# i2c_rom.net
KiCad netlist of a schematic drawn in EAGLE
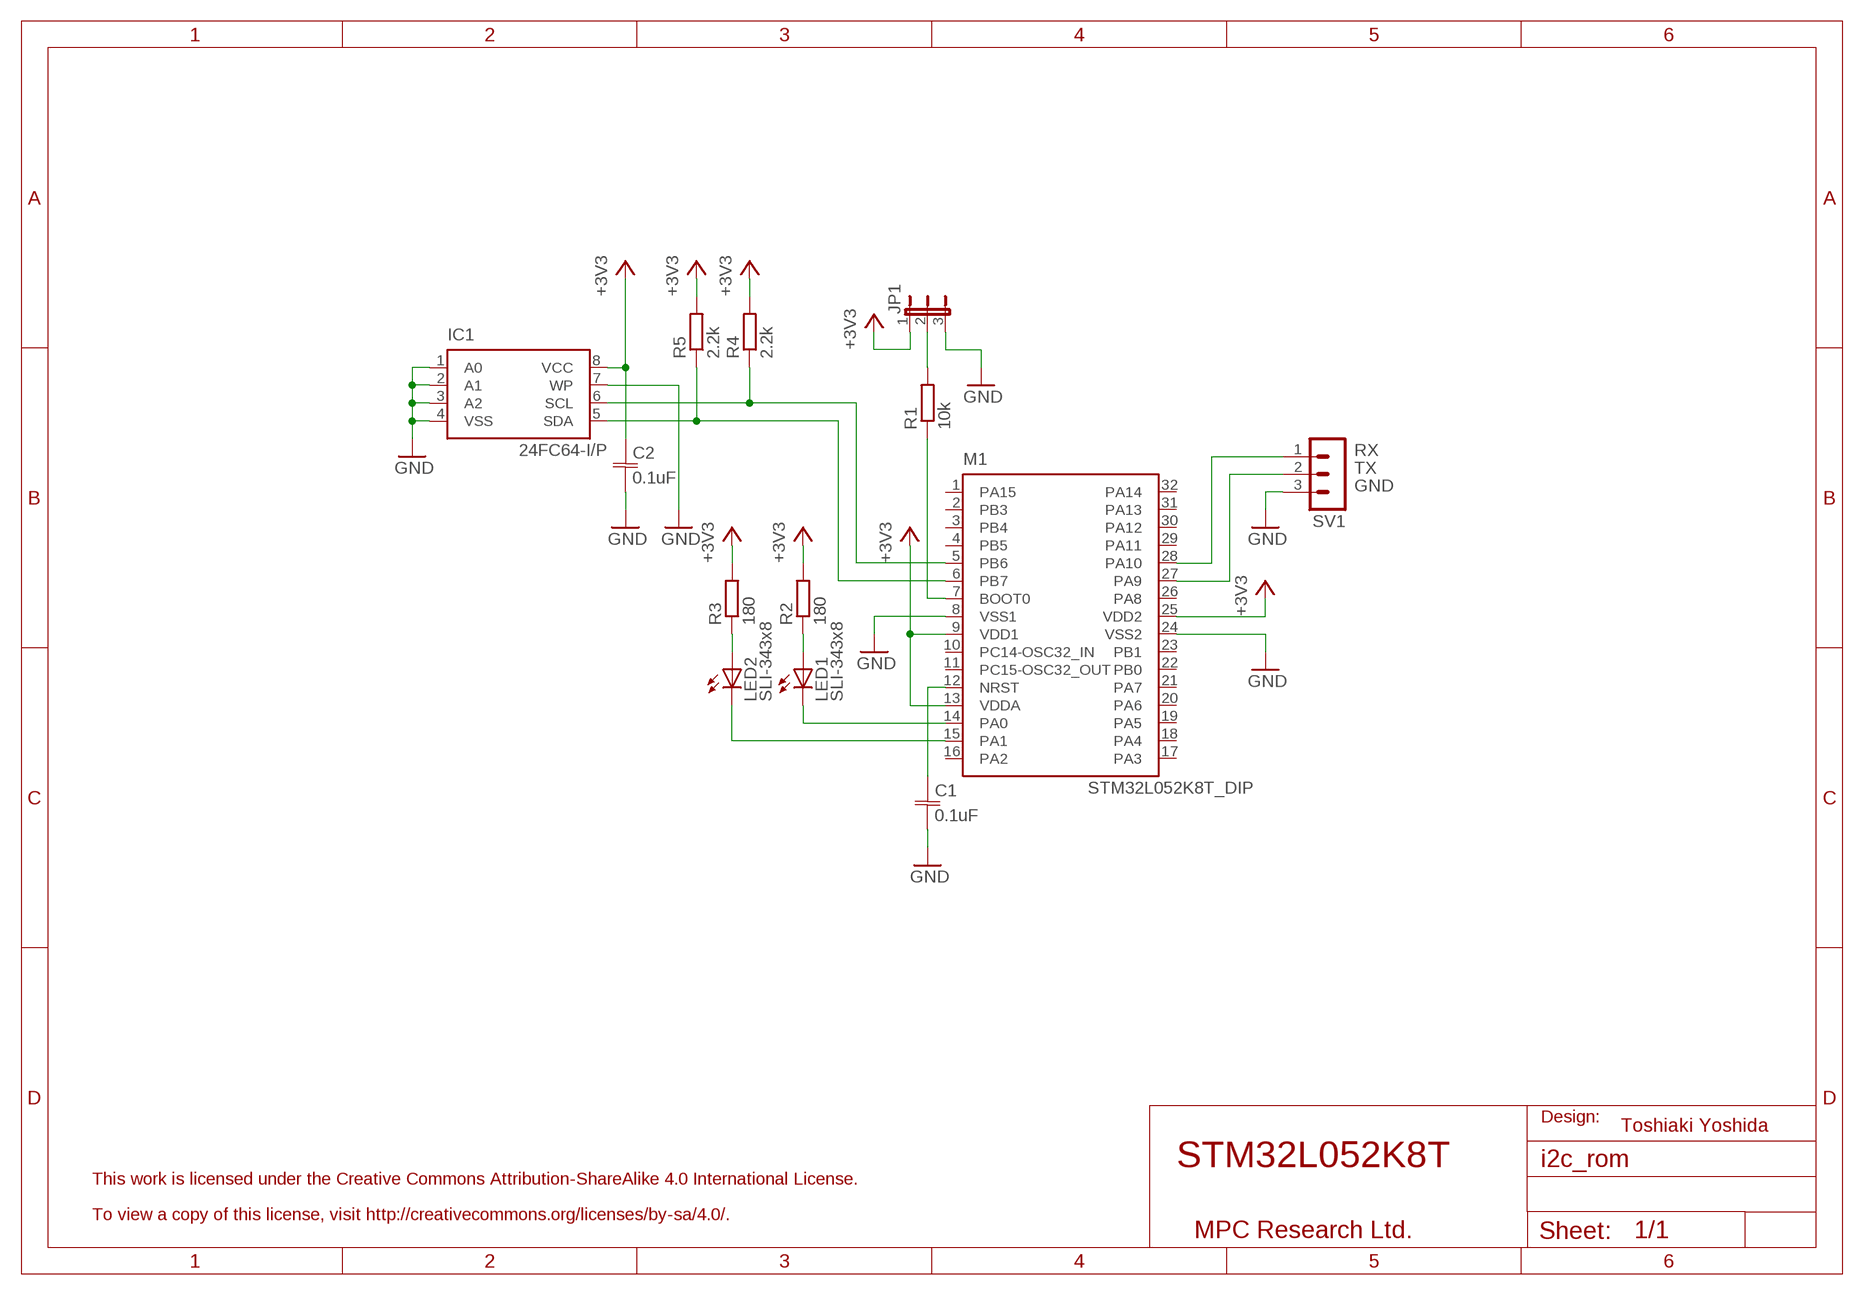
[diagram p0: schematic, sheet 1]

(export (version "E")
  (design (tool "Eeschema 10.0.6"))
  (components
    (comp (ref "C1")
      (value "0.1uF")
      (footprint "eagle-import:C050-024X044")
      (libsource (lib "eagle-import") (part "C-JIS050-024X044"))
    )
    (comp (ref "C2")
      (value "0.1uF")
      (footprint "eagle-import:C050-024X044")
      (libsource (lib "eagle-import") (part "C-JIS050-024X044"))
    )
    (comp (ref "IC1")
      (value "24FC64-I/P")
      (footprint "eagle-import:DIL8")
      (libsource (lib "eagle-import") (part "24/PFC64-I"))
    )
    (comp (ref "JP1")
      (value "JP2E")
      (footprint "eagle-import:JP2")
      (libsource (lib "eagle-import") (part "JP2E"))
    )
    (comp (ref "LED1")
      (value "SLI-343x8")
      (footprint "eagle-import:LED3MM")
      (libsource (lib "eagle-import") (part "LED3MM"))
    )
    (comp (ref "LED2")
      (value "SLI-343x8")
      (footprint "eagle-import:LED3MM")
      (libsource (lib "eagle-import") (part "LED3MM"))
    )
    (comp (ref "M1")
      (value "STM32L052K8T_DIP")
      (footprint "eagle-import:DIP32")
      (libsource (lib "eagle-import") (part "STM32L052K8T_DIP"))
    )
    (comp (ref "R1")
      (value "10k")
      (footprint "eagle-import:0207_2V")
      (libsource (lib "eagle-import") (part "R-EU_0207/2V"))
    )
    (comp (ref "R2")
      (value "180")
      (footprint "eagle-import:0207_2V")
      (libsource (lib "eagle-import") (part "R-EU_0207/2V"))
    )
    (comp (ref "R3")
      (value "180")
      (footprint "eagle-import:0207_2V")
      (libsource (lib "eagle-import") (part "R-EU_0207/2V"))
    )
    (comp (ref "R4")
      (value "2.2k")
      (footprint "eagle-import:0207_2V")
      (libsource (lib "eagle-import") (part "R-EU_0207/2V"))
    )
    (comp (ref "R5")
      (value "2.2k")
      (footprint "eagle-import:0207_2V")
      (libsource (lib "eagle-import") (part "R-EU_0207/2V"))
    )
    (comp (ref "SV1")
      (value "MA03-1")
      (footprint "eagle-import:MA03-1")
      (libsource (lib "eagle-import") (part "MA03-1"))
    )
  )
  (nets
    (net (code "1") (name "+3V3") (class "Default")
      (node (ref "C2") (pin "1") (pinfunction "1_1") (pintype "passive"))
      (node (ref "IC1") (pin "8") (pinfunction "VCC_8") (pintype "power_in"))
      (node (ref "JP1") (pin "1") (pinfunction "1_1") (pintype "passive"))
      (node (ref "M1") (pin "13") (pinfunction "VDDA_13") (pintype "power_in"))
      (node (ref "M1") (pin "25") (pinfunction "VDD2_25") (pintype "bidirectional"))
      (node (ref "M1") (pin "9") (pinfunction "VDD1_9") (pintype "power_in"))
      (node (ref "R2") (pin "2") (pinfunction "2_2") (pintype "passive"))
      (node (ref "R3") (pin "2") (pinfunction "2_2") (pintype "passive"))
      (node (ref "R4") (pin "2") (pinfunction "2_2") (pintype "passive"))
      (node (ref "R5") (pin "2") (pinfunction "2_2") (pintype "passive"))
    )
    (net (code "2") (name "GND") (class "Default")
      (node (ref "C1") (pin "2") (pinfunction "2_2") (pintype "passive"))
      (node (ref "C2") (pin "2") (pinfunction "2_2") (pintype "passive"))
      (node (ref "IC1") (pin "1") (pinfunction "A0_1") (pintype "input"))
      (node (ref "IC1") (pin "2") (pinfunction "A1_2") (pintype "input"))
      (node (ref "IC1") (pin "3") (pinfunction "A2_3") (pintype "input"))
      (node (ref "IC1") (pin "4") (pinfunction "VSS_4") (pintype "power_in"))
      (node (ref "IC1") (pin "7") (pinfunction "WP_7") (pintype "input"))
      (node (ref "JP1") (pin "3") (pinfunction "3_3") (pintype "passive"))
      (node (ref "M1") (pin "24") (pinfunction "VSS2_24") (pintype "power_in"))
      (node (ref "M1") (pin "8") (pinfunction "VSS1_8") (pintype "power_in"))
      (node (ref "SV1") (pin "3") (pinfunction "3_3") (pintype "passive"))
    )
    (net (code "3") (name "Net-(IC1-SCL)") (class "Default")
      (node (ref "IC1") (pin "6") (pinfunction "SCL_6") (pintype "input"))
      (node (ref "M1") (pin "5") (pinfunction "PB6_5") (pintype "bidirectional"))
      (node (ref "R4") (pin "1") (pinfunction "1_1") (pintype "passive"))
    )
    (net (code "4") (name "Net-(IC1-SDA)") (class "Default")
      (node (ref "IC1") (pin "5") (pinfunction "SDA_5") (pintype "open_collector"))
      (node (ref "M1") (pin "6") (pinfunction "PB7_6") (pintype "bidirectional"))
      (node (ref "R5") (pin "1") (pinfunction "1_1") (pintype "passive"))
    )
    (net (code "5") (name "Net-(JP1-Pad2)") (class "Default")
      (node (ref "JP1") (pin "2") (pinfunction "2_2") (pintype "passive"))
      (node (ref "R1") (pin "2") (pinfunction "2_2") (pintype "passive"))
    )
    (net (code "6") (name "Net-(LED1-C)") (class "Default")
      (node (ref "LED1") (pin "K") (pinfunction "C_K") (pintype "passive"))
      (node (ref "M1") (pin "14") (pinfunction "PA0_14") (pintype "bidirectional"))
    )
    (net (code "7") (name "Net-(LED1-PadA)") (class "Default")
      (node (ref "LED1") (pin "A") (pinfunction "A_A") (pintype "passive"))
      (node (ref "R2") (pin "1") (pinfunction "1_1") (pintype "passive"))
    )
    (net (code "8") (name "Net-(LED2-C)") (class "Default")
      (node (ref "LED2") (pin "K") (pinfunction "C_K") (pintype "passive"))
      (node (ref "M1") (pin "15") (pinfunction "PA1_15") (pintype "bidirectional"))
    )
    (net (code "9") (name "Net-(LED2-PadA)") (class "Default")
      (node (ref "LED2") (pin "A") (pinfunction "A_A") (pintype "passive"))
      (node (ref "R3") (pin "1") (pinfunction "1_1") (pintype "passive"))
    )
    (net (code "10") (name "Net-(M1-BOOT0)") (class "Default")
      (node (ref "M1") (pin "7") (pinfunction "BOOT0_7") (pintype "bidirectional"))
      (node (ref "R1") (pin "1") (pinfunction "1_1") (pintype "passive"))
    )
    (net (code "11") (name "Net-(M1-NRST)") (class "Default")
      (node (ref "C1") (pin "1") (pinfunction "1_1") (pintype "passive"))
      (node (ref "M1") (pin "12") (pinfunction "NRST_12") (pintype "bidirectional"))
    )
    (net (code "12") (name "Net-(M1-PA9)") (class "Default")
      (node (ref "M1") (pin "27") (pinfunction "PA9_27") (pintype "bidirectional"))
      (node (ref "SV1") (pin "2") (pinfunction "2_2") (pintype "passive"))
    )
    (net (code "13") (name "Net-(M1-PA10)") (class "Default")
      (node (ref "M1") (pin "28") (pinfunction "PA10_28") (pintype "bidirectional"))
      (node (ref "SV1") (pin "1") (pinfunction "1_1") (pintype "passive"))
    )
    (net (code "14") (name "unconnected-(M1-PA2-Pad16)") (class "Default")
      (node (ref "M1") (pin "16") (pinfunction "PA2_16") (pintype "bidirectional"))
    )
    (net (code "15") (name "unconnected-(M1-PA3-Pad17)") (class "Default")
      (node (ref "M1") (pin "17") (pinfunction "PA3_17") (pintype "bidirectional"))
    )
    (net (code "16") (name "unconnected-(M1-PA4-Pad18)") (class "Default")
      (node (ref "M1") (pin "18") (pinfunction "PA4_18") (pintype "bidirectional"))
    )
    (net (code "17") (name "unconnected-(M1-PA5-Pad19)") (class "Default")
      (node (ref "M1") (pin "19") (pinfunction "PA5_19") (pintype "bidirectional"))
    )
    (net (code "18") (name "unconnected-(M1-PA6-Pad20)") (class "Default")
      (node (ref "M1") (pin "20") (pinfunction "PA6_20") (pintype "bidirectional"))
    )
    (net (code "19") (name "unconnected-(M1-PA7-Pad21)") (class "Default")
      (node (ref "M1") (pin "21") (pinfunction "PA7_21") (pintype "bidirectional"))
    )
    (net (code "20") (name "unconnected-(M1-PA8-Pad26)") (class "Default")
      (node (ref "M1") (pin "26") (pinfunction "PA8_26") (pintype "bidirectional"))
    )
    (net (code "21") (name "unconnected-(M1-PA11-Pad29)") (class "Default")
      (node (ref "M1") (pin "29") (pinfunction "PA11_29") (pintype "bidirectional"))
    )
    (net (code "22") (name "unconnected-(M1-PA12-Pad30)") (class "Default")
      (node (ref "M1") (pin "30") (pinfunction "PA12_30") (pintype "bidirectional"))
    )
    (net (code "23") (name "unconnected-(M1-PA13-Pad31)") (class "Default")
      (node (ref "M1") (pin "31") (pinfunction "PA13_31") (pintype "bidirectional"))
    )
    (net (code "24") (name "unconnected-(M1-PA14-Pad32)") (class "Default")
      (node (ref "M1") (pin "32") (pinfunction "PA14_32") (pintype "bidirectional"))
    )
    (net (code "25") (name "unconnected-(M1-PA15-Pad1)") (class "Default")
      (node (ref "M1") (pin "1") (pinfunction "PA15_1") (pintype "bidirectional"))
    )
    (net (code "26") (name "unconnected-(M1-PB0-Pad22)") (class "Default")
      (node (ref "M1") (pin "22") (pinfunction "PB0_22") (pintype "bidirectional"))
    )
    (net (code "27") (name "unconnected-(M1-PB1-Pad23)") (class "Default")
      (node (ref "M1") (pin "23") (pinfunction "PB1_23") (pintype "bidirectional"))
    )
    (net (code "28") (name "unconnected-(M1-PB3-Pad2)") (class "Default")
      (node (ref "M1") (pin "2") (pinfunction "PB3_2") (pintype "bidirectional"))
    )
    (net (code "29") (name "unconnected-(M1-PB4-Pad3)") (class "Default")
      (node (ref "M1") (pin "3") (pinfunction "PB4_3") (pintype "bidirectional"))
    )
    (net (code "30") (name "unconnected-(M1-PB5-Pad4)") (class "Default")
      (node (ref "M1") (pin "4") (pinfunction "PB5_4") (pintype "bidirectional"))
    )
    (net (code "31") (name "unconnected-(M1-PC14-OSC32_IN-Pad10)") (class "Default")
      (node (ref "M1") (pin "10") (pinfunction "PC14-OSC32_IN_10") (pintype "bidirectional"))
    )
    (net (code "32") (name "unconnected-(M1-PC15-OSC32_OUT-Pad11)") (class "Default")
      (node (ref "M1") (pin "11") (pinfunction "PC15-OSC32_OUT_11") (pintype "bidirectional"))
    )
  )
)
